# xo106-pth.net
KiCad netlist of a schematic drawn in EAGLE
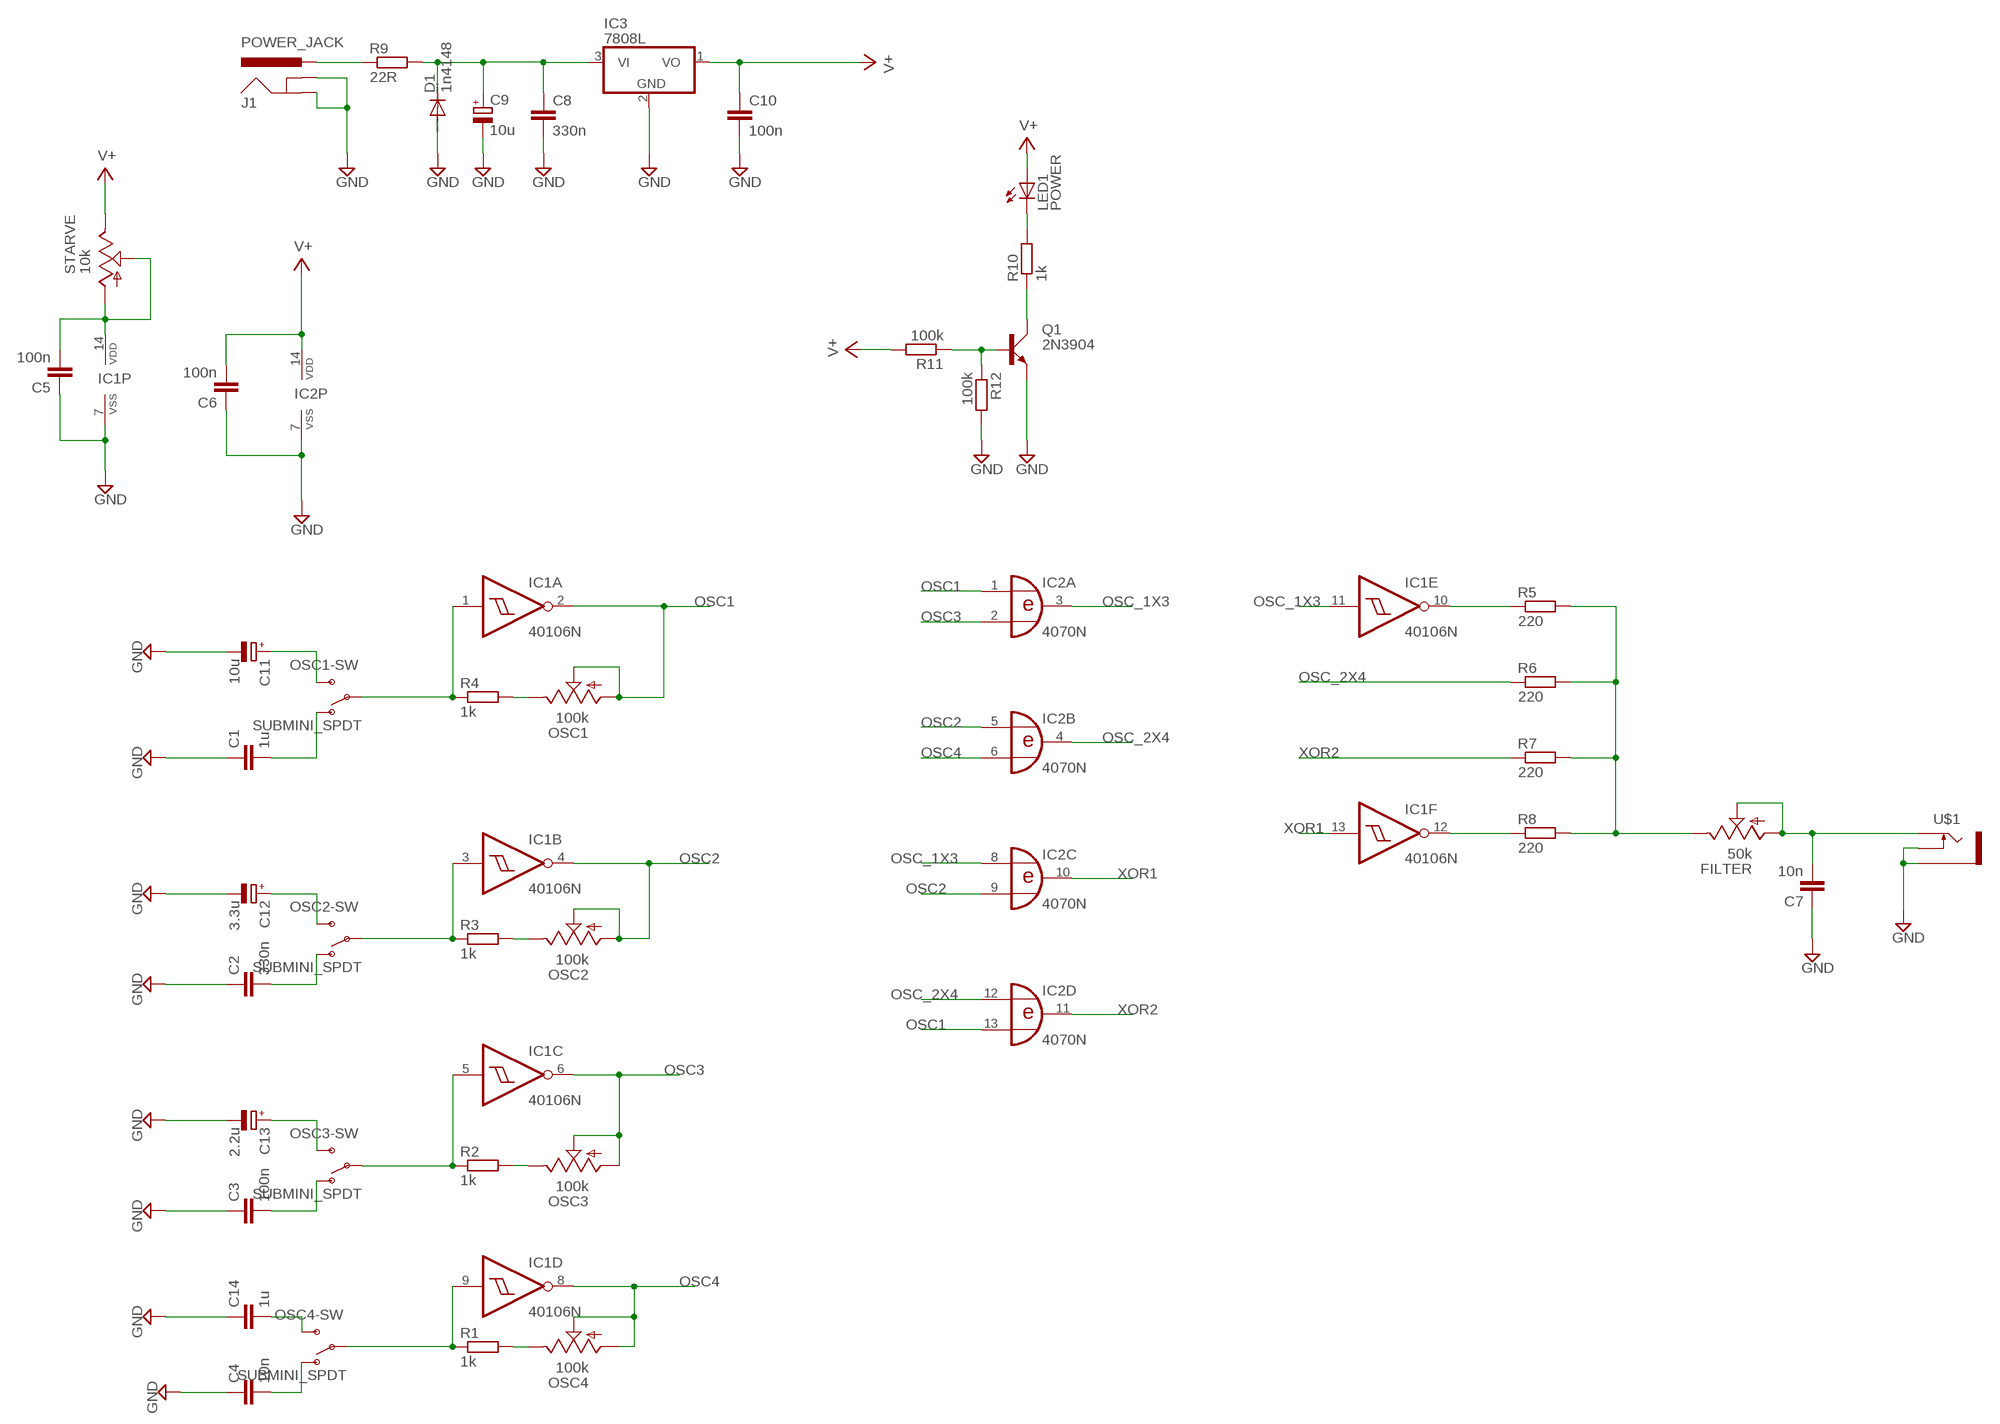
[diagram p0: schematic, sheet 1]

(export (version "E")
  (design (tool "Eeschema 10.0.6"))
  (components
    (comp (ref "C1")
      (value "1u")
      (footprint "eagle-import:C050-025X075")
      (libsource (lib "eagle-import") (part "C-EU050-025X075"))
    )
    (comp (ref "C2")
      (value "330n")
      (footprint "eagle-import:C050-025X075")
      (libsource (lib "eagle-import") (part "C-EU050-025X075"))
    )
    (comp (ref "C3")
      (value "100n")
      (footprint "eagle-import:C050-025X075")
      (libsource (lib "eagle-import") (part "C-EU050-025X075"))
    )
    (comp (ref "C4")
      (value "10n")
      (footprint "eagle-import:C050-025X075")
      (libsource (lib "eagle-import") (part "C-EU050-025X075"))
    )
    (comp (ref "C5")
      (value "100n")
      (footprint "eagle-import:C025-025X050")
      (libsource (lib "eagle-import") (part "C-EU025-025X050"))
    )
    (comp (ref "C6")
      (value "100n")
      (footprint "eagle-import:C025-025X050")
      (libsource (lib "eagle-import") (part "C-EU025-025X050"))
    )
    (comp (ref "C7")
      (value "10n")
      (footprint "eagle-import:C050-025X075")
      (libsource (lib "eagle-import") (part "C-EU050-025X075"))
    )
    (comp (ref "C8")
      (value "330n")
      (footprint "eagle-import:C025-025X050")
      (libsource (lib "eagle-import") (part "C-EU025-025X050"))
    )
    (comp (ref "C9")
      (value "10u")
      (footprint "eagle-import:E2,5-5")
      (libsource (lib "eagle-import") (part "CPOL-EUE2.5-5"))
    )
    (comp (ref "C10")
      (value "100n")
      (footprint "eagle-import:C025-025X050")
      (libsource (lib "eagle-import") (part "C-EU025-025X050"))
    )
    (comp (ref "C11")
      (value "10u")
      (footprint "eagle-import:E2,5-5")
      (libsource (lib "eagle-import") (part "CPOL-EUE2.5-5"))
    )
    (comp (ref "C12")
      (value "3.3u")
      (footprint "eagle-import:E2,5-5")
      (libsource (lib "eagle-import") (part "CPOL-EUE2.5-5"))
    )
    (comp (ref "C13")
      (value "2.2u")
      (footprint "eagle-import:E2,5-5")
      (libsource (lib "eagle-import") (part "CPOL-EUE2.5-5"))
    )
    (comp (ref "C14")
      (value "1u")
      (footprint "eagle-import:C050-025X075")
      (libsource (lib "eagle-import") (part "C-EU050-025X075"))
    )
    (comp (ref "D1")
      (value "1n4148")
      (footprint "eagle-import:D-2.5")
      (libsource (lib "eagle-import") (part "DIODE-D-2.5"))
    )
    (comp (ref "FILTER")
      (value "50k")
      (footprint "eagle-import:9MM_SNAP-IN_POT")
      (libsource (lib "eagle-import") (part "9MM_SNAP-IN_POT_"))
    )
    (comp (ref "IC1")
      (value "40106N")
      (footprint "eagle-import:DIL14")
      (libsource (lib "eagle-import") (part "40106N"))
    )
    (comp (ref "IC2")
      (value "4070N")
      (footprint "eagle-import:DIL14")
      (libsource (lib "eagle-import") (part "4070N"))
    )
    (comp (ref "IC3")
      (value "7808L")
      (footprint "eagle-import:TO92")
      (libsource (lib "eagle-import") (part "78L08"))
    )
    (comp (ref "J1")
      (value "POWER_JACK")
      (footprint "eagle-import:POWER_JACK_PTH")
      (libsource (lib "eagle-import") (part "POWER_JACK"))
    )
    (comp (ref "LED1")
      (value "POWER")
      (footprint "eagle-import:LED3MM")
      (libsource (lib "eagle-import") (part "LED3MM"))
    )
    (comp (ref "OSC1")
      (value "100k")
      (footprint "eagle-import:9MM_SNAP-IN_POT")
      (libsource (lib "eagle-import") (part "9MM_SNAP-IN_POT_"))
    )
    (comp (ref "OSC1-SW")
      (value "SUBMINI_SPDT")
      (footprint "eagle-import:SUBMINI_TOGGLE")
      (libsource (lib "eagle-import") (part "SUBMINI_SPDT"))
    )
    (comp (ref "OSC2")
      (value "100k")
      (footprint "eagle-import:9MM_SNAP-IN_POT")
      (libsource (lib "eagle-import") (part "9MM_SNAP-IN_POT_"))
    )
    (comp (ref "OSC2-SW")
      (value "SUBMINI_SPDT")
      (footprint "eagle-import:SUBMINI_TOGGLE")
      (libsource (lib "eagle-import") (part "SUBMINI_SPDT"))
    )
    (comp (ref "OSC3")
      (value "100k")
      (footprint "eagle-import:9MM_SNAP-IN_POT")
      (libsource (lib "eagle-import") (part "9MM_SNAP-IN_POT_"))
    )
    (comp (ref "OSC3-SW")
      (value "SUBMINI_SPDT")
      (footprint "eagle-import:SUBMINI_TOGGLE")
      (libsource (lib "eagle-import") (part "SUBMINI_SPDT"))
    )
    (comp (ref "OSC4")
      (value "100k")
      (footprint "eagle-import:9MM_SNAP-IN_POT")
      (libsource (lib "eagle-import") (part "9MM_SNAP-IN_POT_"))
    )
    (comp (ref "OSC4-SW")
      (value "SUBMINI_SPDT")
      (footprint "eagle-import:SUBMINI_TOGGLE")
      (libsource (lib "eagle-import") (part "SUBMINI_SPDT"))
    )
    (comp (ref "Q1")
      (value "2N3904")
      (footprint "eagle-import:TO92D")
      (libsource (lib "eagle-import") (part "2N3904"))
    )
    (comp (ref "R1")
      (value "1k")
      (footprint "eagle-import:0207_2V")
      (libsource (lib "eagle-import") (part "R-EU_0207/2V"))
    )
    (comp (ref "R2")
      (value "1k")
      (footprint "eagle-import:0207_2V")
      (libsource (lib "eagle-import") (part "R-EU_0207/2V"))
    )
    (comp (ref "R3")
      (value "1k")
      (footprint "eagle-import:0207_2V")
      (libsource (lib "eagle-import") (part "R-EU_0207/2V"))
    )
    (comp (ref "R4")
      (value "1k")
      (footprint "eagle-import:0207_2V")
      (libsource (lib "eagle-import") (part "R-EU_0207/2V"))
    )
    (comp (ref "R5")
      (value "220")
      (footprint "eagle-import:0207_2V")
      (libsource (lib "eagle-import") (part "R-EU_0207/2V"))
    )
    (comp (ref "R6")
      (value "220")
      (footprint "eagle-import:0207_2V")
      (libsource (lib "eagle-import") (part "R-EU_0207/2V"))
    )
    (comp (ref "R7")
      (value "220")
      (footprint "eagle-import:0207_2V")
      (libsource (lib "eagle-import") (part "R-EU_0207/2V"))
    )
    (comp (ref "R8")
      (value "220")
      (footprint "eagle-import:0207_2V")
      (libsource (lib "eagle-import") (part "R-EU_0207/2V"))
    )
    (comp (ref "R9")
      (value "22R")
      (footprint "eagle-import:0207_2V")
      (libsource (lib "eagle-import") (part "R-EU_0207/2V"))
    )
    (comp (ref "R10")
      (value "1k")
      (footprint "eagle-import:0207_2V")
      (libsource (lib "eagle-import") (part "R-EU_0207/2V"))
    )
    (comp (ref "R11")
      (value "100k")
      (footprint "eagle-import:0207_2V")
      (libsource (lib "eagle-import") (part "R-EU_0207/2V"))
    )
    (comp (ref "R12")
      (value "100k")
      (footprint "eagle-import:0207_2V")
      (libsource (lib "eagle-import") (part "R-EU_0207/2V"))
    )
    (comp (ref "STARVE")
      (value "10k")
      (footprint "eagle-import:9MM_SNAP-IN_POT")
      (libsource (lib "eagle-import") (part "9MM_SNAP-IN_POT_"))
    )
    (comp (ref "U$1")
      (value "PJ302M")
      (footprint "eagle-import:PJ302M")
      (libsource (lib "eagle-import") (part "PJ302M"))
    )
  )
  (nets
    (net (code "1") (name "/OSC1") (class "Default")
      (node (ref "IC1") (pin "2") (pinfunction "O_2") (pintype "output"))
      (node (ref "IC2") (pin "1") (pinfunction "I0_1") (pintype "input"))
      (node (ref "IC2") (pin "13") (pinfunction "I1_13") (pintype "input"))
      (node (ref "OSC1") (pin "1") (pinfunction "A_1") (pintype "passive"))
      (node (ref "OSC1") (pin "2") (pinfunction "S_2") (pintype "passive"))
    )
    (net (code "2") (name "/OSC2") (class "Default")
      (node (ref "IC1") (pin "4") (pinfunction "O_4") (pintype "output"))
      (node (ref "IC2") (pin "5") (pinfunction "I0_5") (pintype "input"))
      (node (ref "IC2") (pin "9") (pinfunction "I1_9") (pintype "input"))
      (node (ref "OSC2") (pin "1") (pinfunction "A_1") (pintype "passive"))
      (node (ref "OSC2") (pin "2") (pinfunction "S_2") (pintype "passive"))
    )
    (net (code "3") (name "/OSC3") (class "Default")
      (node (ref "IC1") (pin "6") (pinfunction "O_6") (pintype "output"))
      (node (ref "IC2") (pin "2") (pinfunction "I1_2") (pintype "input"))
      (node (ref "OSC3") (pin "1") (pinfunction "A_1") (pintype "passive"))
      (node (ref "OSC3") (pin "2") (pinfunction "S_2") (pintype "passive"))
    )
    (net (code "4") (name "/OSC4") (class "Default")
      (node (ref "IC1") (pin "8") (pinfunction "O_8") (pintype "output"))
      (node (ref "IC2") (pin "6") (pinfunction "I1_6") (pintype "input"))
      (node (ref "OSC4") (pin "1") (pinfunction "A_1") (pintype "passive"))
      (node (ref "OSC4") (pin "2") (pinfunction "S_2") (pintype "passive"))
    )
    (net (code "5") (name "/OSC_1X3") (class "Default")
      (node (ref "IC1") (pin "11") (pinfunction "I_11") (pintype "input"))
      (node (ref "IC2") (pin "3") (pinfunction "O_3") (pintype "output"))
      (node (ref "IC2") (pin "8") (pinfunction "I0_8") (pintype "input"))
    )
    (net (code "6") (name "/OSC_2X4") (class "Default")
      (node (ref "IC2") (pin "12") (pinfunction "I0_12") (pintype "input"))
      (node (ref "IC2") (pin "4") (pinfunction "O_4") (pintype "output"))
      (node (ref "R6") (pin "1") (pinfunction "1_1") (pintype "passive"))
    )
    (net (code "7") (name "/XOR1") (class "Default")
      (node (ref "IC1") (pin "13") (pinfunction "I_13") (pintype "input"))
      (node (ref "IC2") (pin "10") (pinfunction "O_10") (pintype "output"))
    )
    (net (code "8") (name "/XOR2") (class "Default")
      (node (ref "IC2") (pin "11") (pinfunction "O_11") (pintype "output"))
      (node (ref "R7") (pin "1") (pinfunction "1_1") (pintype "passive"))
    )
    (net (code "9") (name "GND") (class "Default")
      (node (ref "C1") (pin "1") (pinfunction "1_1") (pintype "passive"))
      (node (ref "C10") (pin "2") (pinfunction "2_2") (pintype "passive"))
      (node (ref "C11") (pin "-") (pinfunction "-_-") (pintype "passive"))
      (node (ref "C12") (pin "-") (pinfunction "-_-") (pintype "passive"))
      (node (ref "C13") (pin "-") (pinfunction "-_-") (pintype "passive"))
      (node (ref "C14") (pin "1") (pinfunction "1_1") (pintype "passive"))
      (node (ref "C2") (pin "1") (pinfunction "1_1") (pintype "passive"))
      (node (ref "C3") (pin "1") (pinfunction "1_1") (pintype "passive"))
      (node (ref "C4") (pin "1") (pinfunction "1_1") (pintype "passive"))
      (node (ref "C5") (pin "1") (pinfunction "1_1") (pintype "passive"))
      (node (ref "C6") (pin "1") (pinfunction "1_1") (pintype "passive"))
      (node (ref "C7") (pin "1") (pinfunction "1_1") (pintype "passive"))
      (node (ref "C8") (pin "2") (pinfunction "2_2") (pintype "passive"))
      (node (ref "C9") (pin "-") (pinfunction "-_-") (pintype "passive"))
      (node (ref "D1") (pin "A") (pinfunction "A_A") (pintype "passive"))
      (node (ref "IC1") (pin "7") (pinfunction "VSS_7") (pintype "power_in"))
      (node (ref "IC2") (pin "7") (pinfunction "VSS_7") (pintype "power_in"))
      (node (ref "IC3") (pin "2") (pinfunction "GND_2") (pintype "passive"))
      (node (ref "J1") (pin "GND") (pinfunction "GND_GND") (pintype "bidirectional"))
      (node (ref "J1") (pin "GNDBREAK") (pinfunction "GNDBREAK_GNDBREAK") (pintype "bidirectional"))
      (node (ref "Q1") (pin "E") (pinfunction "E_E") (pintype "passive"))
      (node (ref "R12") (pin "2") (pinfunction "2_2") (pintype "passive"))
      (node (ref "U$1") (pin "GND") (pinfunction "SLEEVE_GND") (pintype "passive"))
      (node (ref "U$1") (pin "SW") (pinfunction "SWITCH_SW") (pintype "passive"))
    )
    (net (code "10") (name "Net-(FILTER-A)") (class "Default")
      (node (ref "C7") (pin "2") (pinfunction "2_2") (pintype "passive"))
      (node (ref "FILTER") (pin "1") (pinfunction "A_1") (pintype "passive"))
      (node (ref "FILTER") (pin "2") (pinfunction "S_2") (pintype "passive"))
      (node (ref "U$1") (pin "TIP") (pinfunction "TIP_TIP") (pintype "passive"))
    )
    (net (code "11") (name "Net-(FILTER-E)") (class "Default")
      (node (ref "FILTER") (pin "3") (pinfunction "E_3") (pintype "passive"))
      (node (ref "R5") (pin "2") (pinfunction "2_2") (pintype "passive"))
      (node (ref "R6") (pin "2") (pinfunction "2_2") (pintype "passive"))
      (node (ref "R7") (pin "2") (pinfunction "2_2") (pintype "passive"))
      (node (ref "R8") (pin "2") (pinfunction "2_2") (pintype "passive"))
    )
    (net (code "12") (name "Net-(IC1A-I)") (class "Default")
      (node (ref "IC1") (pin "1") (pinfunction "I_1") (pintype "input"))
      (node (ref "OSC1-SW") (pin "COM") (pinfunction "COMMON_COM") (pintype "passive"))
      (node (ref "R4") (pin "1") (pinfunction "1_1") (pintype "passive"))
    )
    (net (code "13") (name "Net-(IC1B-I)") (class "Default")
      (node (ref "IC1") (pin "3") (pinfunction "I_3") (pintype "input"))
      (node (ref "OSC2-SW") (pin "COM") (pinfunction "COMMON_COM") (pintype "passive"))
      (node (ref "R3") (pin "1") (pinfunction "1_1") (pintype "passive"))
    )
    (net (code "14") (name "Net-(IC1C-I)") (class "Default")
      (node (ref "IC1") (pin "5") (pinfunction "I_5") (pintype "input"))
      (node (ref "OSC3-SW") (pin "COM") (pinfunction "COMMON_COM") (pintype "passive"))
      (node (ref "R2") (pin "1") (pinfunction "1_1") (pintype "passive"))
    )
    (net (code "15") (name "Net-(IC1D-I)") (class "Default")
      (node (ref "IC1") (pin "9") (pinfunction "I_9") (pintype "input"))
      (node (ref "OSC4-SW") (pin "COM") (pinfunction "COMMON_COM") (pintype "passive"))
      (node (ref "R1") (pin "1") (pinfunction "1_1") (pintype "passive"))
    )
    (net (code "16") (name "Net-(IC1E-O)") (class "Default")
      (node (ref "IC1") (pin "10") (pinfunction "O_10") (pintype "output"))
      (node (ref "R5") (pin "1") (pinfunction "1_1") (pintype "passive"))
    )
    (net (code "17") (name "Net-(IC1F-O)") (class "Default")
      (node (ref "IC1") (pin "12") (pinfunction "O_12") (pintype "output"))
      (node (ref "R8") (pin "1") (pinfunction "1_1") (pintype "passive"))
    )
    (net (code "18") (name "Net-(IC1G-VDD)") (class "Default")
      (node (ref "C5") (pin "2") (pinfunction "2_2") (pintype "passive"))
      (node (ref "IC1") (pin "14") (pinfunction "VDD_14") (pintype "power_in"))
      (node (ref "STARVE") (pin "1") (pinfunction "A_1") (pintype "passive"))
      (node (ref "STARVE") (pin "2") (pinfunction "S_2") (pintype "passive"))
    )
    (net (code "19") (name "Net-(IC3-VI)") (class "Default")
      (node (ref "C8") (pin "1") (pinfunction "1_1") (pintype "passive"))
      (node (ref "C9") (pin "+") (pinfunction "+_+") (pintype "passive"))
      (node (ref "D1") (pin "C") (pinfunction "C_C") (pintype "passive"))
      (node (ref "IC3") (pin "3") (pinfunction "VI_3") (pintype "input"))
      (node (ref "R9") (pin "2") (pinfunction "2_2") (pintype "passive"))
    )
    (net (code "20") (name "Net-(J1-PadPWR)") (class "Default")
      (node (ref "J1") (pin "PWR") (pinfunction "PWR_PWR") (pintype "bidirectional"))
      (node (ref "R9") (pin "1") (pinfunction "1_1") (pintype "passive"))
    )
    (net (code "21") (name "Net-(LED1-C)") (class "Default")
      (node (ref "LED1") (pin "K") (pinfunction "C_K") (pintype "passive"))
      (node (ref "R10") (pin "2") (pinfunction "2_2") (pintype "passive"))
    )
    (net (code "22") (name "Net-(OSC1-E)") (class "Default")
      (node (ref "OSC1") (pin "3") (pinfunction "E_3") (pintype "passive"))
      (node (ref "R4") (pin "2") (pinfunction "2_2") (pintype "passive"))
    )
    (net (code "23") (name "Net-(OSC1-SW-O)") (class "Default")
      (node (ref "C1") (pin "2") (pinfunction "2_2") (pintype "passive"))
      (node (ref "OSC1-SW") (pin "1") (pinfunction "O_1") (pintype "passive"))
    )
    (net (code "24") (name "Net-(OSC1-SW-S)") (class "Default")
      (node (ref "C11") (pin "+") (pinfunction "+_+") (pintype "passive"))
      (node (ref "OSC1-SW") (pin "3") (pinfunction "S_3") (pintype "passive"))
    )
    (net (code "25") (name "Net-(OSC2-E)") (class "Default")
      (node (ref "OSC2") (pin "3") (pinfunction "E_3") (pintype "passive"))
      (node (ref "R3") (pin "2") (pinfunction "2_2") (pintype "passive"))
    )
    (net (code "26") (name "Net-(OSC2-SW-O)") (class "Default")
      (node (ref "C2") (pin "2") (pinfunction "2_2") (pintype "passive"))
      (node (ref "OSC2-SW") (pin "1") (pinfunction "O_1") (pintype "passive"))
    )
    (net (code "27") (name "Net-(OSC2-SW-S)") (class "Default")
      (node (ref "C12") (pin "+") (pinfunction "+_+") (pintype "passive"))
      (node (ref "OSC2-SW") (pin "3") (pinfunction "S_3") (pintype "passive"))
    )
    (net (code "28") (name "Net-(OSC3-E)") (class "Default")
      (node (ref "OSC3") (pin "3") (pinfunction "E_3") (pintype "passive"))
      (node (ref "R2") (pin "2") (pinfunction "2_2") (pintype "passive"))
    )
    (net (code "29") (name "Net-(OSC3-SW-O)") (class "Default")
      (node (ref "C3") (pin "2") (pinfunction "2_2") (pintype "passive"))
      (node (ref "OSC3-SW") (pin "1") (pinfunction "O_1") (pintype "passive"))
    )
    (net (code "30") (name "Net-(OSC3-SW-S)") (class "Default")
      (node (ref "C13") (pin "+") (pinfunction "+_+") (pintype "passive"))
      (node (ref "OSC3-SW") (pin "3") (pinfunction "S_3") (pintype "passive"))
    )
    (net (code "31") (name "Net-(OSC4-E)") (class "Default")
      (node (ref "OSC4") (pin "3") (pinfunction "E_3") (pintype "passive"))
      (node (ref "R1") (pin "2") (pinfunction "2_2") (pintype "passive"))
    )
    (net (code "32") (name "Net-(OSC4-SW-O)") (class "Default")
      (node (ref "C4") (pin "2") (pinfunction "2_2") (pintype "passive"))
      (node (ref "OSC4-SW") (pin "1") (pinfunction "O_1") (pintype "passive"))
    )
    (net (code "33") (name "Net-(OSC4-SW-S)") (class "Default")
      (node (ref "C14") (pin "2") (pinfunction "2_2") (pintype "passive"))
      (node (ref "OSC4-SW") (pin "3") (pinfunction "S_3") (pintype "passive"))
    )
    (net (code "34") (name "Net-(Q1-PadB)") (class "Default")
      (node (ref "Q1") (pin "B") (pinfunction "B_B") (pintype "passive"))
      (node (ref "R11") (pin "1") (pinfunction "1_1") (pintype "passive"))
      (node (ref "R12") (pin "1") (pinfunction "1_1") (pintype "passive"))
    )
    (net (code "35") (name "Net-(Q1-PadC)") (class "Default")
      (node (ref "Q1") (pin "C") (pinfunction "C_C") (pintype "passive"))
      (node (ref "R10") (pin "1") (pinfunction "1_1") (pintype "passive"))
    )
    (net (code "36") (name "V+") (class "Default")
      (node (ref "C10") (pin "1") (pinfunction "1_1") (pintype "passive"))
      (node (ref "C6") (pin "2") (pinfunction "2_2") (pintype "passive"))
      (node (ref "IC2") (pin "14") (pinfunction "VDD_14") (pintype "power_in"))
      (node (ref "IC3") (pin "1") (pinfunction "VO_1") (pintype "passive"))
      (node (ref "LED1") (pin "A") (pinfunction "A_A") (pintype "passive"))
      (node (ref "R11") (pin "2") (pinfunction "2_2") (pintype "passive"))
      (node (ref "STARVE") (pin "3") (pinfunction "E_3") (pintype "passive"))
    )
  )
)
